# Atrix_adapter.net
KiCad netlist of a schematic drawn in EAGLE
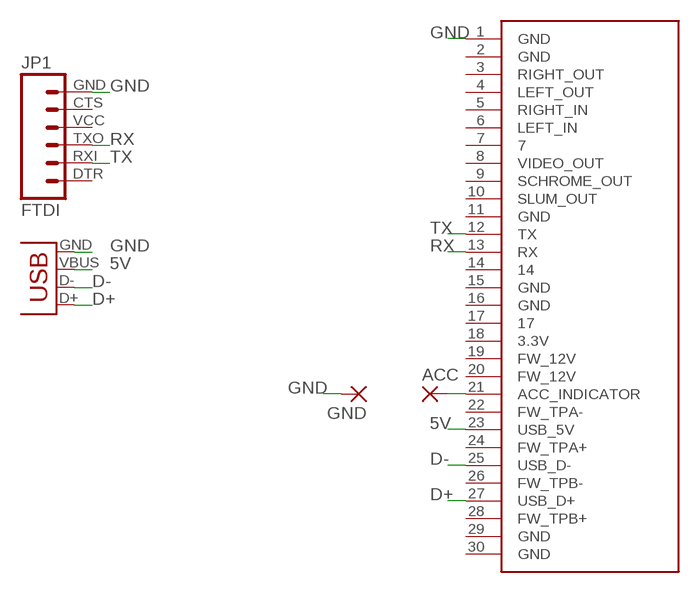
[diagram p0: schematic, sheet 1]

(export (version "E")
  (design (tool "Eeschema 10.0.6"))
  (components
    (comp (ref "ACC")
      (value "1,6/0,9")
      (footprint "eagle-import:1,6_0,9")
      (libsource (lib "eagle-import") (part "1,6/0,9"))
    )
    (comp (ref "GND")
      (value "1,6/0,9")
      (footprint "eagle-import:1,6_0,9")
      (libsource (lib "eagle-import") (part "1,6/0,9"))
    )
    (comp (ref "JP1")
      (value "FTDI")
      (footprint "eagle-import:FTDI_BASIC")
      (libsource (lib "eagle-import") (part "FTDI_BASICPTH"))
    )
    (comp (ref "U$1")
      (value "IPOD_CONNECTOR_MALE")
      (footprint "eagle-import:IPOD_MALE_CONNECTOR")
      (libsource (lib "eagle-import") (part "IPOD_CONNECTOR_MALE"))
    )
    (comp (ref "X1")
      (value "USB-MICROB")
      (footprint "eagle-import:USB-MICROB")
      (libsource (lib "eagle-import") (part "USB-MICROB"))
    )
  )
  (nets
    (net (code "1") (name "/5V") (class "Default")
      (node (ref "U$1") (pin "23") (pinfunction "USB_5V_23") (pintype "bidirectional"))
      (node (ref "X1") (pin "VBUS") (pinfunction "VBUS_VBUS") (pintype "bidirectional"))
    )
    (net (code "2") (name "/D+") (class "Default")
      (node (ref "U$1") (pin "27") (pinfunction "USB_D+_27") (pintype "bidirectional"))
      (node (ref "X1") (pin "D+") (pinfunction "D+_D+") (pintype "bidirectional"))
    )
    (net (code "3") (name "/D-") (class "Default")
      (node (ref "U$1") (pin "25") (pinfunction "USB_D-_25") (pintype "bidirectional"))
      (node (ref "X1") (pin "D-") (pinfunction "D-_D-") (pintype "bidirectional"))
    )
    (net (code "4") (name "/GND") (class "Default")
      (node (ref "GND") (pin "1") (pinfunction "P_1") (pintype "passive"))
      (node (ref "JP1") (pin "GND") (pinfunction "6_GND") (pintype "passive"))
      (node (ref "U$1") (pin "1") (pinfunction "GND_1") (pintype "bidirectional"))
      (node (ref "X1") (pin "GND") (pinfunction "GND_GND") (pintype "bidirectional"))
    )
    (net (code "5") (name "/RX") (class "Default")
      (node (ref "JP1") (pin "TXO") (pinfunction "3_TXO") (pintype "passive"))
      (node (ref "U$1") (pin "13") (pinfunction "RX_13") (pintype "bidirectional"))
    )
    (net (code "6") (name "/TX") (class "Default")
      (node (ref "JP1") (pin "RXI") (pinfunction "2_RXI") (pintype "passive"))
      (node (ref "U$1") (pin "12") (pinfunction "TX_12") (pintype "bidirectional"))
    )
    (net (code "7") (name "Net-(ACC-P)") (class "Default")
      (node (ref "ACC") (pin "1") (pinfunction "P_1") (pintype "passive"))
      (node (ref "U$1") (pin "21") (pinfunction "ACC_INDICATOR_21") (pintype "bidirectional"))
    )
    (net (code "8") (name "unconnected-(JP1-1-PadDTR)") (class "Default")
      (node (ref "JP1") (pin "DTR") (pinfunction "1_DTR") (pintype "passive"))
    )
    (net (code "9") (name "unconnected-(JP1-4-PadVCC)") (class "Default")
      (node (ref "JP1") (pin "VCC") (pinfunction "4_VCC") (pintype "passive"))
    )
    (net (code "10") (name "unconnected-(JP1-5-PadCTS)") (class "Default")
      (node (ref "JP1") (pin "CTS") (pinfunction "5_CTS") (pintype "passive"))
    )
    (net (code "11") (name "unconnected-(U$1-3.3V-Pad18)") (class "Default")
      (node (ref "U$1") (pin "18") (pinfunction "3.3V_18") (pintype "bidirectional"))
    )
    (net (code "12") (name "unconnected-(U$1-FW_12V-Pad19)") (class "Default")
      (node (ref "U$1") (pin "19") (pinfunction "FW_12V_19") (pintype "bidirectional"))
    )
    (net (code "13") (name "unconnected-(U$1-FW_12V-Pad20)") (class "Default")
      (node (ref "U$1") (pin "20") (pinfunction "FW_12V_20") (pintype "bidirectional"))
    )
    (net (code "14") (name "unconnected-(U$1-FW_TPA+-Pad24)") (class "Default")
      (node (ref "U$1") (pin "24") (pinfunction "FW_TPA+_24") (pintype "bidirectional"))
    )
    (net (code "15") (name "unconnected-(U$1-FW_TPA--Pad22)") (class "Default")
      (node (ref "U$1") (pin "22") (pinfunction "FW_TPA-_22") (pintype "bidirectional"))
    )
    (net (code "16") (name "unconnected-(U$1-FW_TPB+-Pad28)") (class "Default")
      (node (ref "U$1") (pin "28") (pinfunction "FW_TPB+_28") (pintype "bidirectional"))
    )
    (net (code "17") (name "unconnected-(U$1-FW_TPB--Pad26)") (class "Default")
      (node (ref "U$1") (pin "26") (pinfunction "FW_TPB-_26") (pintype "bidirectional"))
    )
    (net (code "18") (name "unconnected-(U$1-GND-Pad2)") (class "Default")
      (node (ref "U$1") (pin "2") (pinfunction "GND_2") (pintype "bidirectional"))
    )
    (net (code "19") (name "unconnected-(U$1-GND-Pad11)") (class "Default")
      (node (ref "U$1") (pin "11") (pinfunction "GND_11") (pintype "bidirectional"))
    )
    (net (code "20") (name "unconnected-(U$1-GND-Pad15)") (class "Default")
      (node (ref "U$1") (pin "15") (pinfunction "GND_15") (pintype "bidirectional"))
    )
    (net (code "21") (name "unconnected-(U$1-GND-Pad16)") (class "Default")
      (node (ref "U$1") (pin "16") (pinfunction "GND_16") (pintype "bidirectional"))
    )
    (net (code "22") (name "unconnected-(U$1-GND-Pad29)") (class "Default")
      (node (ref "U$1") (pin "29") (pinfunction "GND_29") (pintype "bidirectional"))
    )
    (net (code "23") (name "unconnected-(U$1-GND-Pad30)") (class "Default")
      (node (ref "U$1") (pin "30") (pinfunction "GND_30") (pintype "bidirectional"))
    )
    (net (code "24") (name "unconnected-(U$1-LEFT_IN-Pad6)") (class "Default")
      (node (ref "U$1") (pin "6") (pinfunction "LEFT_IN_6") (pintype "bidirectional"))
    )
    (net (code "25") (name "unconnected-(U$1-LEFT_OUT-Pad4)") (class "Default")
      (node (ref "U$1") (pin "4") (pinfunction "LEFT_OUT_4") (pintype "bidirectional"))
    )
    (net (code "26") (name "unconnected-(U$1-Pad7)") (class "Default")
      (node (ref "U$1") (pin "7") (pinfunction "7_7") (pintype "bidirectional"))
    )
    (net (code "27") (name "unconnected-(U$1-Pad14)") (class "Default")
      (node (ref "U$1") (pin "14") (pinfunction "14_14") (pintype "bidirectional"))
    )
    (net (code "28") (name "unconnected-(U$1-Pad17)") (class "Default")
      (node (ref "U$1") (pin "17") (pinfunction "17_17") (pintype "bidirectional"))
    )
    (net (code "29") (name "unconnected-(U$1-RIGHT_IN-Pad5)") (class "Default")
      (node (ref "U$1") (pin "5") (pinfunction "RIGHT_IN_5") (pintype "bidirectional"))
    )
    (net (code "30") (name "unconnected-(U$1-RIGHT_OUT-Pad3)") (class "Default")
      (node (ref "U$1") (pin "3") (pinfunction "RIGHT_OUT_3") (pintype "bidirectional"))
    )
    (net (code "31") (name "unconnected-(U$1-SCHROME_OUT-Pad9)") (class "Default")
      (node (ref "U$1") (pin "9") (pinfunction "SCHROME_OUT_9") (pintype "bidirectional"))
    )
    (net (code "32") (name "unconnected-(U$1-SLUM_OUT-Pad10)") (class "Default")
      (node (ref "U$1") (pin "10") (pinfunction "SLUM_OUT_10") (pintype "bidirectional"))
    )
    (net (code "33") (name "unconnected-(U$1-VIDEO_OUT-Pad8)") (class "Default")
      (node (ref "U$1") (pin "8") (pinfunction "VIDEO_OUT_8") (pintype "bidirectional"))
    )
  )
)
